# Z80_DEV_BOARD_REV_1.net
KiCad netlist of a schematic drawn in EAGLE
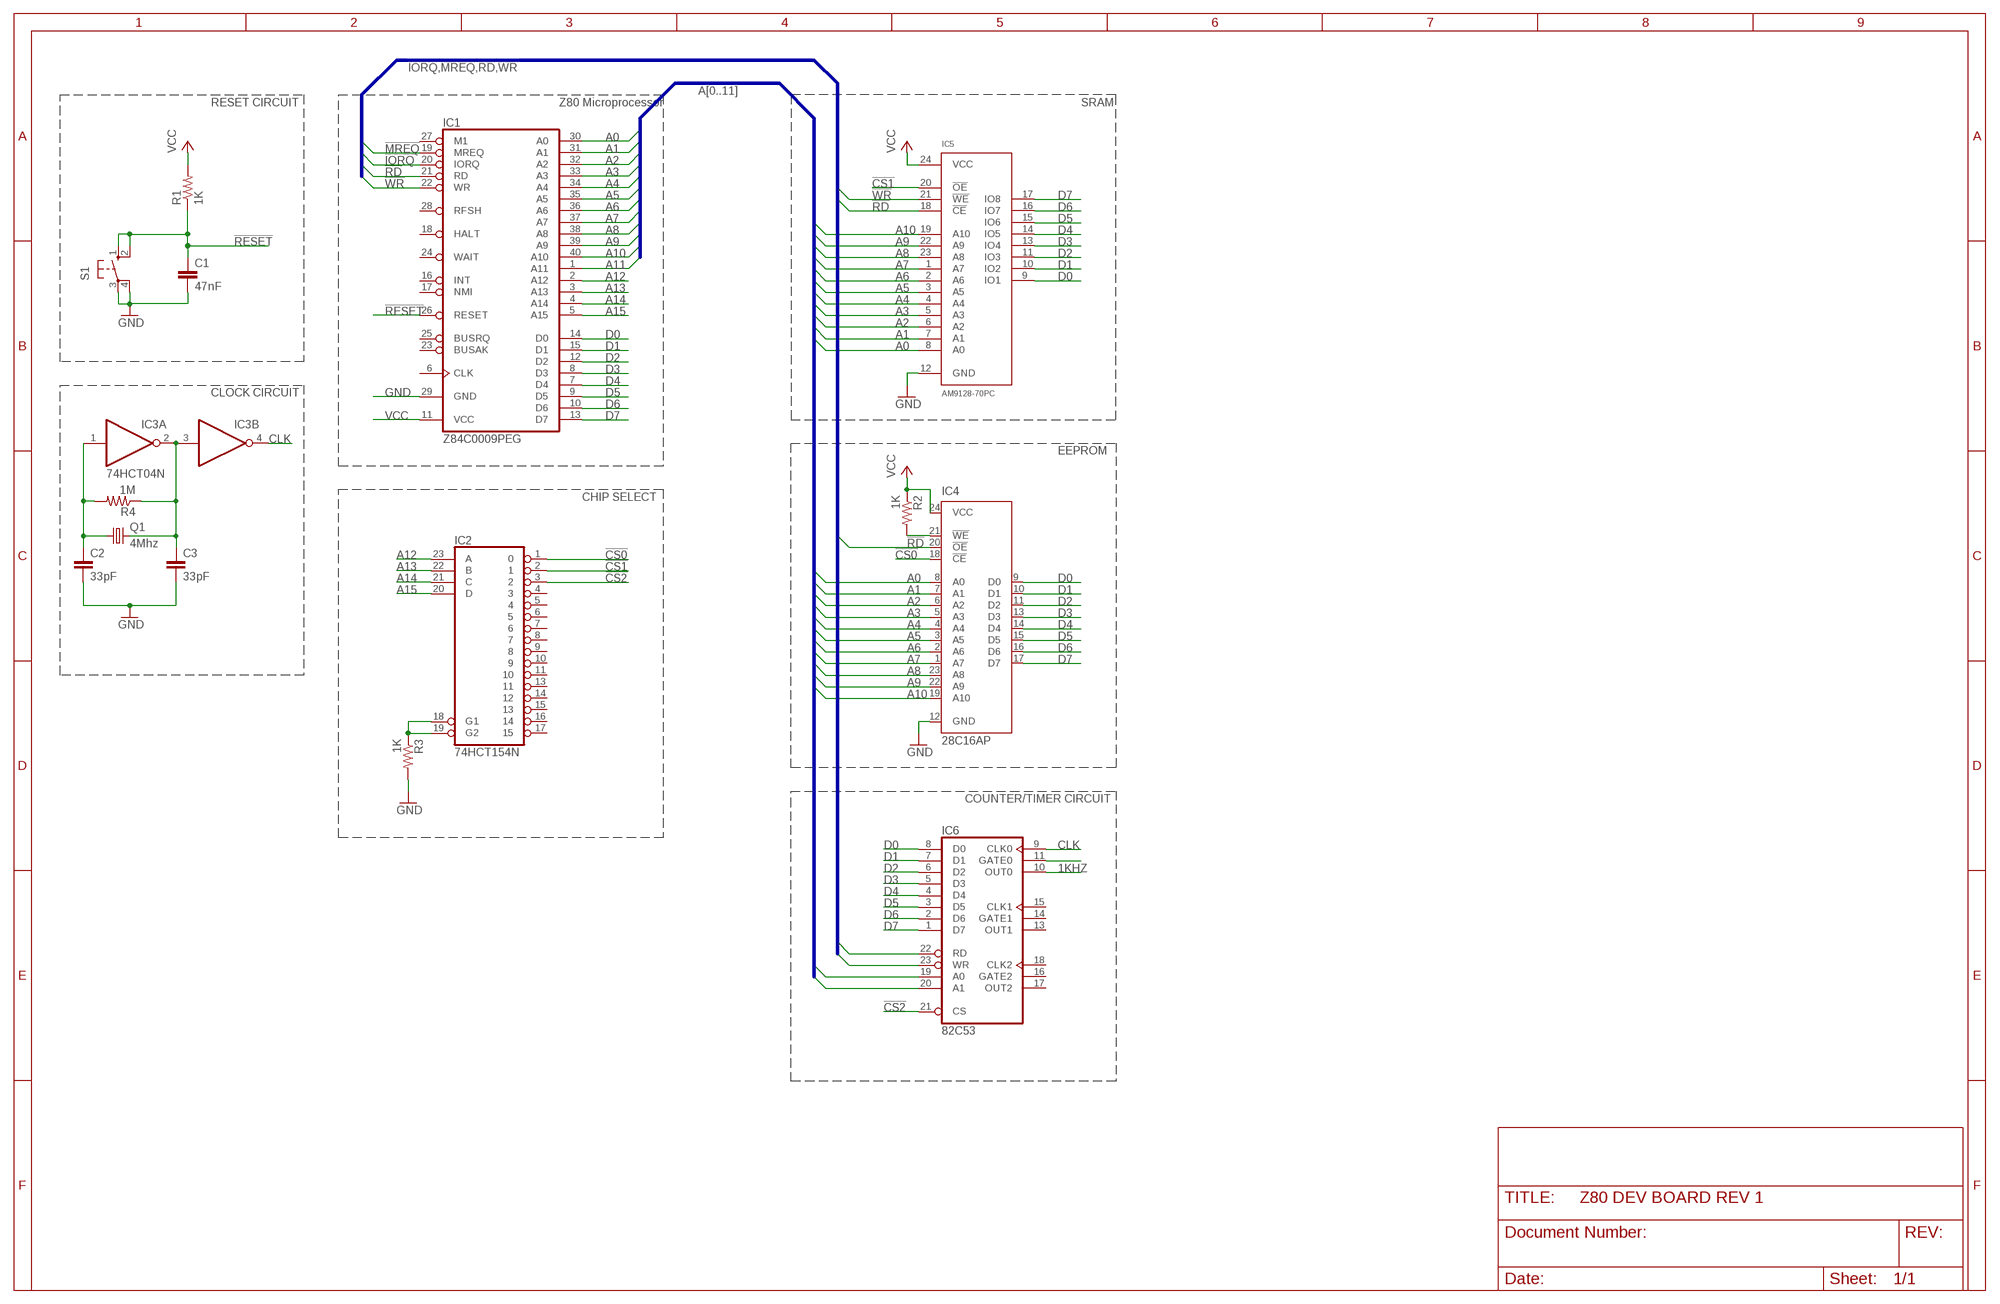
[diagram p0: schematic, sheet 1]

(export (version "E")
  (design (tool "Eeschema 10.0.6"))
  (components
    (comp (ref "C1")
      (value "47nF")
      (footprint "eagle-import:C050-035X075")
      (libsource (lib "eagle-import") (part "C-EU050-035X075"))
    )
    (comp (ref "C2")
      (value "33pF")
      (footprint "eagle-import:C050-035X075")
      (libsource (lib "eagle-import") (part "C-EU050-035X075"))
    )
    (comp (ref "C3")
      (value "33pF")
      (footprint "eagle-import:C050-035X075")
      (libsource (lib "eagle-import") (part "C-EU050-035X075"))
    )
    (comp (ref "IC1")
      (value "Z84C0009PEG")
      (footprint "eagle-import:DIL40")
      (libsource (lib "eagle-import") (part "Z80CPU"))
    )
    (comp (ref "IC2")
      (value "74HCT154N")
      (footprint "eagle-import:DIL24-6")
      (libsource (lib "eagle-import") (part "74154NHCT"))
    )
    (comp (ref "IC3")
      (value "74HCT04N")
      (footprint "eagle-import:DIL14")
      (libsource (lib "eagle-import") (part "7404NHCT"))
    )
    (comp (ref "IC4")
      (value "28C16AP")
      (footprint "eagle-import:DIL24-6")
      (fields (field (name "MPN") "CAT28C16ALI-12"))
      (libsource (lib "eagle-import") (part "2816APC"))
    )
    (comp (ref "IC5")
      (value "AM9128-70PC")
      (footprint "eagle-import:DIL24-6")
      (libsource (lib "eagle-import") (part "AM9128-70PC"))
    )
    (comp (ref "IC6")
      (value "82C53")
      (footprint "eagle-import:DIL24-6")
      (libsource (lib "eagle-import") (part "8253"))
    )
    (comp (ref "Q1")
      (value "4Mhz")
      (footprint "eagle-import:HC49_S")
      (libsource (lib "eagle-import") (part "CRYSTALHC49S"))
    )
    (comp (ref "R1")
      (value "1K")
      (footprint "eagle-import:0207_7")
      (libsource (lib "eagle-import") (part "R-US_0207/7"))
    )
    (comp (ref "R2")
      (value "1K")
      (footprint "eagle-import:0207_7")
      (libsource (lib "eagle-import") (part "R-US_0207/7"))
    )
    (comp (ref "R3")
      (value "1K")
      (footprint "eagle-import:0207_7")
      (libsource (lib "eagle-import") (part "R-US_0207/7"))
    )
    (comp (ref "R4")
      (value "1M")
      (footprint "eagle-import:0207_7")
      (libsource (lib "eagle-import") (part "R-US_0207/7"))
    )
    (comp (ref "S1")
      (value "10-XX")
      (footprint "eagle-import:B3F-10XX")
      (fields (field (name "MPN") "B3F-1000"))
      (libsource (lib "eagle-import") (part "10-XX"))
    )
  )
  (nets
    (net (code "1") (name "/1KHZ") (class "Default")
      (node (ref "IC6") (pin "10") (pinfunction "OUT0_10") (pintype "output"))
    )
    (net (code "2") (name "/A0") (class "Default")
      (node (ref "IC1") (pin "30") (pinfunction "A0_30") (pintype "output"))
      (node (ref "IC4") (pin "8") (pinfunction "A0_8") (pintype "input"))
      (node (ref "IC5") (pin "8") (pinfunction "A0_8") (pintype "input"))
      (node (ref "IC6") (pin "19") (pinfunction "A0_19") (pintype "input"))
    )
    (net (code "3") (name "/A1") (class "Default")
      (node (ref "IC1") (pin "31") (pinfunction "A1_31") (pintype "output"))
      (node (ref "IC4") (pin "7") (pinfunction "A1_7") (pintype "input"))
      (node (ref "IC5") (pin "7") (pinfunction "A1_7") (pintype "input"))
      (node (ref "IC6") (pin "20") (pinfunction "A1_20") (pintype "input"))
    )
    (net (code "4") (name "/A2") (class "Default")
      (node (ref "IC1") (pin "32") (pinfunction "A2_32") (pintype "output"))
      (node (ref "IC4") (pin "6") (pinfunction "A2_6") (pintype "input"))
      (node (ref "IC5") (pin "6") (pinfunction "A2_6") (pintype "input"))
    )
    (net (code "5") (name "/A3") (class "Default")
      (node (ref "IC1") (pin "33") (pinfunction "A3_33") (pintype "output"))
      (node (ref "IC4") (pin "5") (pinfunction "A3_5") (pintype "input"))
      (node (ref "IC5") (pin "5") (pinfunction "A3_5") (pintype "input"))
    )
    (net (code "6") (name "/A4") (class "Default")
      (node (ref "IC1") (pin "34") (pinfunction "A4_34") (pintype "output"))
      (node (ref "IC4") (pin "4") (pinfunction "A4_4") (pintype "input"))
      (node (ref "IC5") (pin "4") (pinfunction "A4_4") (pintype "input"))
    )
    (net (code "7") (name "/A5") (class "Default")
      (node (ref "IC1") (pin "35") (pinfunction "A5_35") (pintype "output"))
      (node (ref "IC4") (pin "3") (pinfunction "A5_3") (pintype "input"))
      (node (ref "IC5") (pin "3") (pinfunction "A5_3") (pintype "input"))
    )
    (net (code "8") (name "/A6") (class "Default")
      (node (ref "IC1") (pin "36") (pinfunction "A6_36") (pintype "output"))
      (node (ref "IC4") (pin "2") (pinfunction "A6_2") (pintype "input"))
      (node (ref "IC5") (pin "2") (pinfunction "A6_2") (pintype "input"))
    )
    (net (code "9") (name "/A7") (class "Default")
      (node (ref "IC1") (pin "37") (pinfunction "A7_37") (pintype "output"))
      (node (ref "IC4") (pin "1") (pinfunction "A7_1") (pintype "input"))
      (node (ref "IC5") (pin "1") (pinfunction "A7_1") (pintype "input"))
    )
    (net (code "10") (name "/A8") (class "Default")
      (node (ref "IC1") (pin "38") (pinfunction "A8_38") (pintype "output"))
      (node (ref "IC4") (pin "23") (pinfunction "A8_23") (pintype "input"))
      (node (ref "IC5") (pin "23") (pinfunction "A8_23") (pintype "input"))
    )
    (net (code "11") (name "/A9") (class "Default")
      (node (ref "IC1") (pin "39") (pinfunction "A9_39") (pintype "output"))
      (node (ref "IC4") (pin "22") (pinfunction "A9_22") (pintype "input"))
      (node (ref "IC5") (pin "22") (pinfunction "A9_22") (pintype "input"))
    )
    (net (code "12") (name "/A10") (class "Default")
      (node (ref "IC1") (pin "40") (pinfunction "A10_40") (pintype "output"))
      (node (ref "IC4") (pin "19") (pinfunction "A10_19") (pintype "input"))
      (node (ref "IC5") (pin "19") (pinfunction "A10_19") (pintype "input"))
    )
    (net (code "13") (name "/A11") (class "Default")
      (node (ref "IC1") (pin "1") (pinfunction "A11_1") (pintype "output"))
    )
    (net (code "14") (name "/A12") (class "Default")
      (node (ref "IC1") (pin "2") (pinfunction "A12_2") (pintype "output"))
      (node (ref "IC2") (pin "23") (pinfunction "A_23") (pintype "input"))
    )
    (net (code "15") (name "/A13") (class "Default")
      (node (ref "IC1") (pin "3") (pinfunction "A13_3") (pintype "output"))
      (node (ref "IC2") (pin "22") (pinfunction "B_22") (pintype "input"))
    )
    (net (code "16") (name "/A14") (class "Default")
      (node (ref "IC1") (pin "4") (pinfunction "A14_4") (pintype "output"))
      (node (ref "IC2") (pin "21") (pinfunction "C_21") (pintype "input"))
    )
    (net (code "17") (name "/A15") (class "Default")
      (node (ref "IC1") (pin "5") (pinfunction "A15_5") (pintype "output"))
      (node (ref "IC2") (pin "20") (pinfunction "D_20") (pintype "input"))
    )
    (net (code "19") (name "/CLK") (class "Default")
      (node (ref "IC3") (pin "4") (pinfunction "O_4") (pintype "output"))
      (node (ref "IC6") (pin "9") (pinfunction "CLK0_9") (pintype "input"))
    )
    (net (code "20") (name "/D0") (class "Default")
      (node (ref "IC1") (pin "14") (pinfunction "D0_14") (pintype "bidirectional"))
      (node (ref "IC4") (pin "9") (pinfunction "D0_9") (pintype "tri_state"))
      (node (ref "IC5") (pin "9") (pinfunction "IO1_9") (pintype "bidirectional"))
      (node (ref "IC6") (pin "8") (pinfunction "D0_8") (pintype "bidirectional"))
    )
    (net (code "21") (name "/D1") (class "Default")
      (node (ref "IC1") (pin "15") (pinfunction "D1_15") (pintype "bidirectional"))
      (node (ref "IC4") (pin "10") (pinfunction "D1_10") (pintype "tri_state"))
      (node (ref "IC5") (pin "10") (pinfunction "IO2_10") (pintype "bidirectional"))
      (node (ref "IC6") (pin "7") (pinfunction "D1_7") (pintype "bidirectional"))
    )
    (net (code "22") (name "/D2") (class "Default")
      (node (ref "IC1") (pin "12") (pinfunction "D2_12") (pintype "bidirectional"))
      (node (ref "IC4") (pin "11") (pinfunction "D2_11") (pintype "tri_state"))
      (node (ref "IC5") (pin "11") (pinfunction "IO3_11") (pintype "bidirectional"))
      (node (ref "IC6") (pin "6") (pinfunction "D2_6") (pintype "bidirectional"))
    )
    (net (code "23") (name "/D3") (class "Default")
      (node (ref "IC1") (pin "8") (pinfunction "D3_8") (pintype "bidirectional"))
      (node (ref "IC4") (pin "13") (pinfunction "D3_13") (pintype "tri_state"))
      (node (ref "IC5") (pin "13") (pinfunction "IO4_13") (pintype "bidirectional"))
      (node (ref "IC6") (pin "5") (pinfunction "D3_5") (pintype "bidirectional"))
    )
    (net (code "24") (name "/D4") (class "Default")
      (node (ref "IC1") (pin "7") (pinfunction "D4_7") (pintype "bidirectional"))
      (node (ref "IC4") (pin "14") (pinfunction "D4_14") (pintype "tri_state"))
      (node (ref "IC5") (pin "14") (pinfunction "IO5_14") (pintype "bidirectional"))
      (node (ref "IC6") (pin "4") (pinfunction "D4_4") (pintype "bidirectional"))
    )
    (net (code "25") (name "/D5") (class "Default")
      (node (ref "IC1") (pin "9") (pinfunction "D5_9") (pintype "bidirectional"))
      (node (ref "IC4") (pin "15") (pinfunction "D5_15") (pintype "tri_state"))
      (node (ref "IC5") (pin "15") (pinfunction "IO6_15") (pintype "bidirectional"))
      (node (ref "IC6") (pin "3") (pinfunction "D5_3") (pintype "bidirectional"))
    )
    (net (code "26") (name "/D6") (class "Default")
      (node (ref "IC1") (pin "10") (pinfunction "D6_10") (pintype "bidirectional"))
      (node (ref "IC4") (pin "16") (pinfunction "D6_16") (pintype "tri_state"))
      (node (ref "IC5") (pin "16") (pinfunction "IO7_16") (pintype "bidirectional"))
      (node (ref "IC6") (pin "2") (pinfunction "D6_2") (pintype "bidirectional"))
    )
    (net (code "27") (name "/D7") (class "Default")
      (node (ref "IC1") (pin "13") (pinfunction "D7_13") (pintype "bidirectional"))
      (node (ref "IC4") (pin "17") (pinfunction "D7_17") (pintype "tri_state"))
      (node (ref "IC5") (pin "17") (pinfunction "IO8_17") (pintype "bidirectional"))
      (node (ref "IC6") (pin "1") (pinfunction "D7_1") (pintype "bidirectional"))
    )
    (net (code "29") (name "/~{CS0}") (class "Default")
      (node (ref "IC2") (pin "1") (pinfunction "0_1") (pintype "output"))
      (node (ref "IC4") (pin "18") (pinfunction "~{CE}_18") (pintype "input"))
    )
    (net (code "30") (name "/~{CS1}") (class "Default")
      (node (ref "IC2") (pin "2") (pinfunction "1_2") (pintype "output"))
      (node (ref "IC5") (pin "20") (pinfunction "~{OE}_20") (pintype "input"))
    )
    (net (code "31") (name "/~{CS2}") (class "Default")
      (node (ref "IC2") (pin "3") (pinfunction "2_3") (pintype "output"))
      (node (ref "IC6") (pin "21") (pinfunction "CS_21") (pintype "input"))
    )
    (net (code "32") (name "/~{IORQ}") (class "Default")
      (node (ref "IC1") (pin "20") (pinfunction "IORQ_20") (pintype "output"))
    )
    (net (code "33") (name "/~{MREQ}") (class "Default")
      (node (ref "IC1") (pin "19") (pinfunction "MREQ_19") (pintype "output"))
    )
    (net (code "34") (name "/~{RD}") (class "Default")
      (node (ref "IC1") (pin "21") (pinfunction "RD_21") (pintype "output"))
      (node (ref "IC4") (pin "20") (pinfunction "~{OE}_20") (pintype "input"))
      (node (ref "IC5") (pin "18") (pinfunction "~{CE}_18") (pintype "input"))
      (node (ref "IC6") (pin "22") (pinfunction "RD_22") (pintype "input"))
    )
    (net (code "35") (name "/~{RESET}") (class "Default")
      (node (ref "C1") (pin "1") (pinfunction "1_1") (pintype "passive"))
      (node (ref "IC1") (pin "26") (pinfunction "RESET_26") (pintype "input"))
      (node (ref "R1") (pin "1") (pinfunction "1_1") (pintype "passive"))
      (node (ref "S1") (pin "1") (pinfunction "S_1") (pintype "passive"))
      (node (ref "S1") (pin "2") (pinfunction "S1_2") (pintype "passive"))
    )
    (net (code "36") (name "/~{WR}") (class "Default")
      (node (ref "IC1") (pin "22") (pinfunction "WR_22") (pintype "output"))
      (node (ref "IC5") (pin "21") (pinfunction "~{WE}_21") (pintype "input"))
      (node (ref "IC6") (pin "23") (pinfunction "WR_23") (pintype "input"))
    )
    (net (code "37") (name "GND") (class "Default")
      (node (ref "C1") (pin "2") (pinfunction "2_2") (pintype "passive"))
      (node (ref "C2") (pin "2") (pinfunction "2_2") (pintype "passive"))
      (node (ref "C3") (pin "2") (pinfunction "2_2") (pintype "passive"))
      (node (ref "IC1") (pin "29") (pinfunction "GND_29") (pintype "power_in"))
      (node (ref "IC4") (pin "12") (pinfunction "GND_12") (pintype "power_in"))
      (node (ref "IC5") (pin "12") (pinfunction "GND_12") (pintype "power_in"))
      (node (ref "R3") (pin "2") (pinfunction "2_2") (pintype "passive"))
      (node (ref "S1") (pin "3") (pinfunction "P_3") (pintype "passive"))
      (node (ref "S1") (pin "4") (pinfunction "P1_4") (pintype "passive"))
    )
    (net (code "38") (name "Net-(IC2A-G1)") (class "Default")
      (node (ref "IC2") (pin "18") (pinfunction "G1_18") (pintype "input"))
      (node (ref "IC2") (pin "19") (pinfunction "G2_19") (pintype "input"))
      (node (ref "R3") (pin "1") (pinfunction "1_1") (pintype "passive"))
    )
    (net (code "39") (name "Net-(IC3A-I)") (class "Default")
      (node (ref "C2") (pin "1") (pinfunction "1_1") (pintype "passive"))
      (node (ref "IC3") (pin "1") (pinfunction "I_1") (pintype "input"))
      (node (ref "Q1") (pin "1") (pinfunction "1_1") (pintype "passive"))
      (node (ref "R4") (pin "2") (pinfunction "2_2") (pintype "passive"))
    )
    (net (code "40") (name "Net-(IC3A-O)") (class "Default")
      (node (ref "C3") (pin "1") (pinfunction "1_1") (pintype "passive"))
      (node (ref "IC3") (pin "2") (pinfunction "O_2") (pintype "output"))
      (node (ref "IC3") (pin "3") (pinfunction "I_3") (pintype "input"))
      (node (ref "Q1") (pin "2") (pinfunction "2_2") (pintype "passive"))
      (node (ref "R4") (pin "1") (pinfunction "1_1") (pintype "passive"))
    )
    (net (code "41") (name "Net-(IC4-~{WE})") (class "Default")
      (node (ref "IC4") (pin "21") (pinfunction "~{WE}_21") (pintype "input"))
      (node (ref "R2") (pin "2") (pinfunction "2_2") (pintype "passive"))
    )
    (net (code "42") (name "VCC") (class "Default")
      (node (ref "IC1") (pin "11") (pinfunction "VCC_11") (pintype "power_in"))
      (node (ref "IC4") (pin "24") (pinfunction "VCC_24") (pintype "power_in"))
      (node (ref "IC5") (pin "24") (pinfunction "VCC_24") (pintype "power_in"))
      (node (ref "R1") (pin "2") (pinfunction "2_2") (pintype "passive"))
      (node (ref "R2") (pin "1") (pinfunction "1_1") (pintype "passive"))
    )
    (net (code "43") (name "unconnected-(IC1-BUSAK-Pad23)") (class "Default")
      (node (ref "IC1") (pin "23") (pinfunction "BUSAK_23") (pintype "output"))
    )
    (net (code "44") (name "unconnected-(IC1-BUSRQ-Pad25)") (class "Default")
      (node (ref "IC1") (pin "25") (pinfunction "BUSRQ_25") (pintype "input"))
    )
    (net (code "45") (name "unconnected-(IC1-CLK-Pad6)") (class "Default")
      (node (ref "IC1") (pin "6") (pinfunction "CLK_6") (pintype "input"))
    )
    (net (code "46") (name "unconnected-(IC1-HALT-Pad18)") (class "Default")
      (node (ref "IC1") (pin "18") (pinfunction "HALT_18") (pintype "output"))
    )
    (net (code "47") (name "unconnected-(IC1-INT-Pad16)") (class "Default")
      (node (ref "IC1") (pin "16") (pinfunction "INT_16") (pintype "input"))
    )
    (net (code "48") (name "unconnected-(IC1-M1-Pad27)") (class "Default")
      (node (ref "IC1") (pin "27") (pinfunction "M1_27") (pintype "output"))
    )
    (net (code "49") (name "unconnected-(IC1-NMI-Pad17)") (class "Default")
      (node (ref "IC1") (pin "17") (pinfunction "NMI_17") (pintype "input"))
    )
    (net (code "50") (name "unconnected-(IC1-RFSH-Pad28)") (class "Default")
      (node (ref "IC1") (pin "28") (pinfunction "RFSH_28") (pintype "output"))
    )
    (net (code "51") (name "unconnected-(IC1-WAIT-Pad24)") (class "Default")
      (node (ref "IC1") (pin "24") (pinfunction "WAIT_24") (pintype "input"))
    )
    (net (code "52") (name "unconnected-(IC2A-3-Pad4)") (class "Default")
      (node (ref "IC2") (pin "4") (pinfunction "3_4") (pintype "output"))
    )
    (net (code "53") (name "unconnected-(IC2A-4-Pad5)") (class "Default")
      (node (ref "IC2") (pin "5") (pinfunction "4_5") (pintype "output"))
    )
    (net (code "54") (name "unconnected-(IC2A-5-Pad6)") (class "Default")
      (node (ref "IC2") (pin "6") (pinfunction "5_6") (pintype "output"))
    )
    (net (code "55") (name "unconnected-(IC2A-6-Pad7)") (class "Default")
      (node (ref "IC2") (pin "7") (pinfunction "6_7") (pintype "output"))
    )
    (net (code "56") (name "unconnected-(IC2A-7-Pad8)") (class "Default")
      (node (ref "IC2") (pin "8") (pinfunction "7_8") (pintype "output"))
    )
    (net (code "57") (name "unconnected-(IC2A-8-Pad9)") (class "Default")
      (node (ref "IC2") (pin "9") (pinfunction "8_9") (pintype "output"))
    )
    (net (code "58") (name "unconnected-(IC2A-9-Pad10)") (class "Default")
      (node (ref "IC2") (pin "10") (pinfunction "9_10") (pintype "output"))
    )
    (net (code "59") (name "unconnected-(IC2A-10-Pad11)") (class "Default")
      (node (ref "IC2") (pin "11") (pinfunction "10_11") (pintype "output"))
    )
    (net (code "60") (name "unconnected-(IC2A-11-Pad13)") (class "Default")
      (node (ref "IC2") (pin "13") (pinfunction "11_13") (pintype "output"))
    )
    (net (code "61") (name "unconnected-(IC2A-12-Pad14)") (class "Default")
      (node (ref "IC2") (pin "14") (pinfunction "12_14") (pintype "output"))
    )
    (net (code "62") (name "unconnected-(IC2A-13-Pad15)") (class "Default")
      (node (ref "IC2") (pin "15") (pinfunction "13_15") (pintype "output"))
    )
    (net (code "63") (name "unconnected-(IC2A-14-Pad16)") (class "Default")
      (node (ref "IC2") (pin "16") (pinfunction "14_16") (pintype "output"))
    )
    (net (code "64") (name "unconnected-(IC2A-15-Pad17)") (class "Default")
      (node (ref "IC2") (pin "17") (pinfunction "15_17") (pintype "output"))
    )
    (net (code "65") (name "unconnected-(IC6A-CLK1-Pad15)") (class "Default")
      (node (ref "IC6") (pin "15") (pinfunction "CLK1_15") (pintype "input"))
    )
    (net (code "66") (name "unconnected-(IC6A-CLK2-Pad18)") (class "Default")
      (node (ref "IC6") (pin "18") (pinfunction "CLK2_18") (pintype "input"))
    )
    (net (code "67") (name "unconnected-(IC6A-GATE0-Pad11)") (class "Default")
      (node (ref "IC6") (pin "11") (pinfunction "GATE0_11") (pintype "input"))
    )
    (net (code "68") (name "unconnected-(IC6A-GATE1-Pad14)") (class "Default")
      (node (ref "IC6") (pin "14") (pinfunction "GATE1_14") (pintype "input"))
    )
    (net (code "69") (name "unconnected-(IC6A-GATE2-Pad16)") (class "Default")
      (node (ref "IC6") (pin "16") (pinfunction "GATE2_16") (pintype "input"))
    )
    (net (code "70") (name "unconnected-(IC6A-OUT1-Pad13)") (class "Default")
      (node (ref "IC6") (pin "13") (pinfunction "OUT1_13") (pintype "output"))
    )
    (net (code "71") (name "unconnected-(IC6A-OUT2-Pad17)") (class "Default")
      (node (ref "IC6") (pin "17") (pinfunction "OUT2_17") (pintype "output"))
    )
  )
)
